# pic32.net
KiCad netlist of a schematic drawn in EAGLE
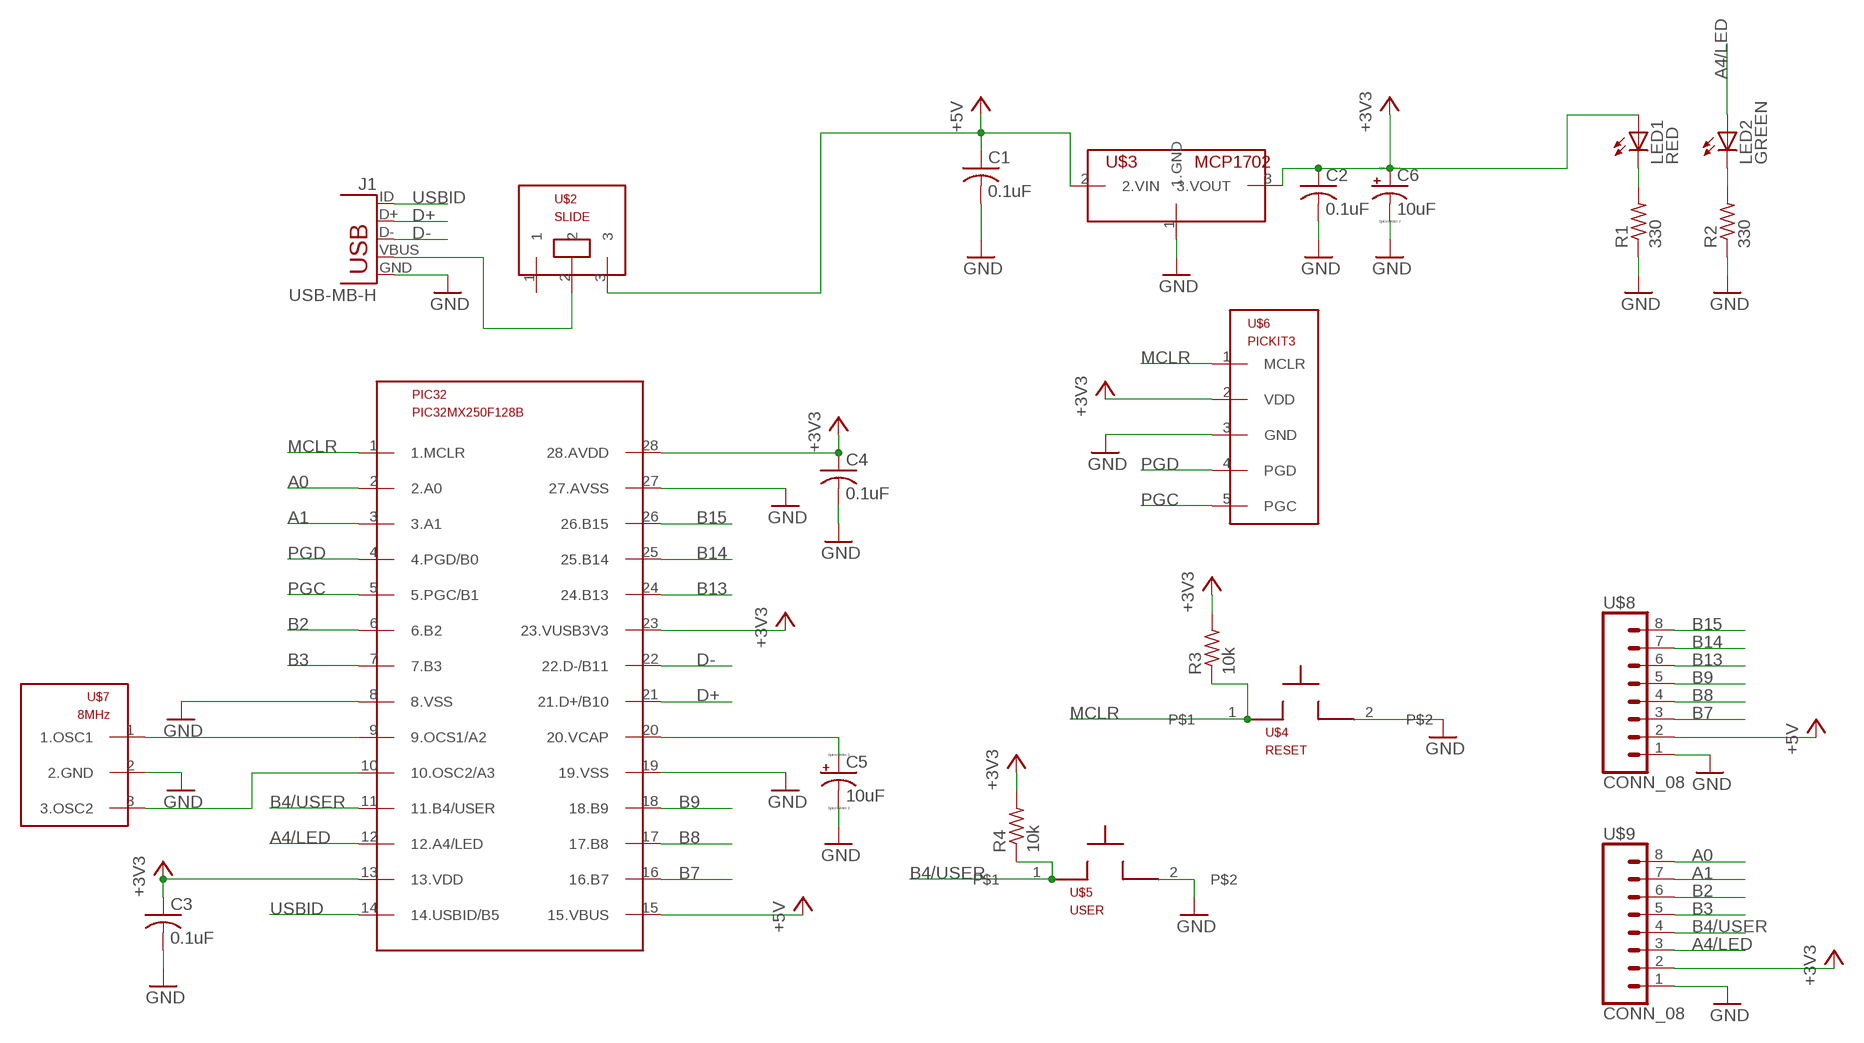
[diagram p0: schematic, sheet 1]

(export (version "E")
  (design (tool "Eeschema 10.0.6"))
  (components
    (comp (ref "C1")
      (value "0.1uF")
      (footprint "eagle-import:C025-025X050")
      (libsource (lib "eagle-import") (part "C-US025-025X050"))
    )
    (comp (ref "C2")
      (value "0.1uF")
      (footprint "eagle-import:C025-025X050")
      (libsource (lib "eagle-import") (part "C-US025-025X050"))
    )
    (comp (ref "C3")
      (value "0.1uF")
      (footprint "eagle-import:C025-025X050")
      (libsource (lib "eagle-import") (part "C-US025-025X050"))
    )
    (comp (ref "C4")
      (value "0.1uF")
      (footprint "eagle-import:C025-025X050")
      (libsource (lib "eagle-import") (part "C-US025-025X050"))
    )
    (comp (ref "C5")
      (value "10uF")
      (footprint "eagle-import:B45181B")
      (libsource (lib "eagle-import") (part "CPOL-USB45181B"))
    )
    (comp (ref "C6")
      (value "10uF")
      (footprint "eagle-import:B45181B")
      (libsource (lib "eagle-import") (part "CPOL-USB45181B"))
    )
    (comp (ref "J1")
      (value "USB-MB-H")
      (footprint "eagle-import:USB-MB-H")
      (libsource (lib "eagle-import") (part "USB-MB-H"))
    )
    (comp (ref "LED1")
      (value "RED")
      (footprint "eagle-import:LED3MM")
      (libsource (lib "eagle-import") (part "LED3MM"))
    )
    (comp (ref "LED2")
      (value "GREEN")
      (footprint "eagle-import:LED3MM")
      (libsource (lib "eagle-import") (part "LED3MM"))
    )
    (comp (ref "PIC32")
      (value "PIC32MX250F128B")
      (footprint "eagle-import:DIL28-3")
      (libsource (lib "eagle-import") (part "PIC32MX250F128B"))
    )
    (comp (ref "R1")
      (value "330")
      (footprint "eagle-import:0207_10")
      (libsource (lib "eagle-import") (part "R-US_0207/10"))
    )
    (comp (ref "R2")
      (value "330")
      (footprint "eagle-import:0207_10")
      (libsource (lib "eagle-import") (part "R-US_0207/10"))
    )
    (comp (ref "R3")
      (value "10k")
      (footprint "eagle-import:0207_10")
      (libsource (lib "eagle-import") (part "R-US_0207/10"))
    )
    (comp (ref "R4")
      (value "10k")
      (footprint "eagle-import:0207_10")
      (libsource (lib "eagle-import") (part "R-US_0207/10"))
    )
    (comp (ref "U$2")
      (value "SLIDE")
      (footprint "eagle-import:SLIDE")
      (libsource (lib "eagle-import") (part "SLIDE"))
    )
    (comp (ref "U$3")
      (value "MCP1702")
      (footprint "eagle-import:TO92")
      (libsource (lib "eagle-import") (part "MCP1702"))
    )
    (comp (ref "U$4")
      (value "RESET")
      (footprint "eagle-import:PB")
      (libsource (lib "eagle-import") (part "PB"))
    )
    (comp (ref "U$5")
      (value "USER")
      (footprint "eagle-import:PB")
      (libsource (lib "eagle-import") (part "PB"))
    )
    (comp (ref "U$6")
      (value "PICKIT3")
      (footprint "eagle-import:1X05")
      (libsource (lib "eagle-import") (part "PICKIT3"))
    )
    (comp (ref "U$7")
      (value "8MHz")
      (footprint "eagle-import:OSC")
      (libsource (lib "eagle-import") (part "OCS"))
    )
    (comp (ref "U$8")
      (value "CONN_08")
      (footprint "eagle-import:1X08")
      (libsource (lib "eagle-import") (part "CONN_08"))
    )
    (comp (ref "U$9")
      (value "CONN_08")
      (footprint "eagle-import:1X08")
      (libsource (lib "eagle-import") (part "CONN_08"))
    )
  )
  (nets
    (net (code "1") (name "+3V3") (class "Default")
      (node (ref "C2") (pin "1") (pinfunction "1_1") (pintype "passive"))
      (node (ref "C3") (pin "1") (pinfunction "1_1") (pintype "passive"))
      (node (ref "C4") (pin "1") (pinfunction "1_1") (pintype "passive"))
      (node (ref "C6") (pin "+") (pinfunction "+_+") (pintype "passive"))
      (node (ref "LED1") (pin "A") (pinfunction "A_A") (pintype "passive"))
      (node (ref "PIC32") (pin "13") (pinfunction "13.VDD_13") (pintype "bidirectional"))
      (node (ref "PIC32") (pin "23") (pinfunction "23.VUSB3V3_23") (pintype "bidirectional"))
      (node (ref "PIC32") (pin "28") (pinfunction "28.AVDD_28") (pintype "bidirectional"))
      (node (ref "R3") (pin "2") (pinfunction "2_2") (pintype "passive"))
      (node (ref "R4") (pin "2") (pinfunction "2_2") (pintype "passive"))
      (node (ref "U$3") (pin "3") (pinfunction "3.VOUT_3") (pintype "bidirectional"))
      (node (ref "U$6") (pin "2") (pinfunction "VDD_2") (pintype "bidirectional"))
      (node (ref "U$9") (pin "2") (pinfunction "2_2") (pintype "passive"))
    )
    (net (code "2") (name "+5V") (class "Default")
      (node (ref "C1") (pin "1") (pinfunction "1_1") (pintype "passive"))
      (node (ref "PIC32") (pin "15") (pinfunction "15.VBUS_15") (pintype "bidirectional"))
      (node (ref "U$2") (pin "3") (pinfunction "3_3") (pintype "bidirectional"))
      (node (ref "U$3") (pin "2") (pinfunction "2.VIN_2") (pintype "bidirectional"))
      (node (ref "U$8") (pin "2") (pinfunction "2_2") (pintype "passive"))
    )
    (net (code "3") (name "/A0") (class "Default")
      (node (ref "PIC32") (pin "2") (pinfunction "2.A0_2") (pintype "bidirectional"))
      (node (ref "U$9") (pin "8") (pinfunction "8_8") (pintype "passive"))
    )
    (net (code "4") (name "/A1") (class "Default")
      (node (ref "PIC32") (pin "3") (pinfunction "3.A1_3") (pintype "bidirectional"))
      (node (ref "U$9") (pin "7") (pinfunction "7_7") (pintype "passive"))
    )
    (net (code "5") (name "/A4{slash}LED") (class "Default")
      (node (ref "LED2") (pin "A") (pinfunction "A_A") (pintype "passive"))
      (node (ref "PIC32") (pin "12") (pinfunction "12.A4/LED_12") (pintype "bidirectional"))
      (node (ref "U$9") (pin "3") (pinfunction "3_3") (pintype "passive"))
    )
    (net (code "6") (name "/B2") (class "Default")
      (node (ref "PIC32") (pin "6") (pinfunction "6.B2_6") (pintype "bidirectional"))
      (node (ref "U$9") (pin "6") (pinfunction "6_6") (pintype "passive"))
    )
    (net (code "7") (name "/B3") (class "Default")
      (node (ref "PIC32") (pin "7") (pinfunction "7.B3_7") (pintype "bidirectional"))
      (node (ref "U$9") (pin "5") (pinfunction "5_5") (pintype "passive"))
    )
    (net (code "8") (name "/B4{slash}USER") (class "Default")
      (node (ref "PIC32") (pin "11") (pinfunction "11.B4/USER_11") (pintype "bidirectional"))
      (node (ref "R4") (pin "1") (pinfunction "1_1") (pintype "passive"))
      (node (ref "U$5") (pin "1") (pinfunction "P$1_1") (pintype "bidirectional"))
      (node (ref "U$9") (pin "4") (pinfunction "4_4") (pintype "passive"))
    )
    (net (code "9") (name "/B7") (class "Default")
      (node (ref "PIC32") (pin "16") (pinfunction "16.B7_16") (pintype "bidirectional"))
      (node (ref "U$8") (pin "3") (pinfunction "3_3") (pintype "passive"))
    )
    (net (code "10") (name "/B8") (class "Default")
      (node (ref "PIC32") (pin "17") (pinfunction "17.B8_17") (pintype "bidirectional"))
      (node (ref "U$8") (pin "4") (pinfunction "4_4") (pintype "passive"))
    )
    (net (code "11") (name "/B9") (class "Default")
      (node (ref "PIC32") (pin "18") (pinfunction "18.B9_18") (pintype "bidirectional"))
      (node (ref "U$8") (pin "5") (pinfunction "5_5") (pintype "passive"))
    )
    (net (code "12") (name "/B13") (class "Default")
      (node (ref "PIC32") (pin "24") (pinfunction "24.B13_24") (pintype "bidirectional"))
      (node (ref "U$8") (pin "6") (pinfunction "6_6") (pintype "passive"))
    )
    (net (code "13") (name "/B14") (class "Default")
      (node (ref "PIC32") (pin "25") (pinfunction "25.B14_25") (pintype "bidirectional"))
      (node (ref "U$8") (pin "7") (pinfunction "7_7") (pintype "passive"))
    )
    (net (code "14") (name "/B15") (class "Default")
      (node (ref "PIC32") (pin "26") (pinfunction "26.B15_26") (pintype "bidirectional"))
      (node (ref "U$8") (pin "8") (pinfunction "8_8") (pintype "passive"))
    )
    (net (code "15") (name "/D+") (class "Default")
      (node (ref "J1") (pin "D+") (pinfunction "D+_D+") (pintype "bidirectional"))
      (node (ref "PIC32") (pin "21") (pinfunction "21.D+/B10_21") (pintype "bidirectional"))
    )
    (net (code "16") (name "/D-") (class "Default")
      (node (ref "J1") (pin "D-") (pinfunction "D-_D-") (pintype "bidirectional"))
      (node (ref "PIC32") (pin "22") (pinfunction "22.D-/B11_22") (pintype "bidirectional"))
    )
    (net (code "17") (name "/MCLR") (class "Default")
      (node (ref "PIC32") (pin "1") (pinfunction "1.MCLR_1") (pintype "bidirectional"))
      (node (ref "R3") (pin "1") (pinfunction "1_1") (pintype "passive"))
      (node (ref "U$4") (pin "1") (pinfunction "P$1_1") (pintype "bidirectional"))
      (node (ref "U$6") (pin "1") (pinfunction "MCLR_1") (pintype "bidirectional"))
    )
    (net (code "18") (name "/PGC") (class "Default")
      (node (ref "PIC32") (pin "5") (pinfunction "5.PGC/B1_5") (pintype "bidirectional"))
      (node (ref "U$6") (pin "5") (pinfunction "PGC_5") (pintype "bidirectional"))
    )
    (net (code "19") (name "/PGD") (class "Default")
      (node (ref "PIC32") (pin "4") (pinfunction "4.PGD/B0_4") (pintype "bidirectional"))
      (node (ref "U$6") (pin "4") (pinfunction "PGD_4") (pintype "bidirectional"))
    )
    (net (code "20") (name "/USBID") (class "Default")
      (node (ref "J1") (pin "ID") (pinfunction "ID_ID") (pintype "bidirectional"))
      (node (ref "PIC32") (pin "14") (pinfunction "14.USBID/B5_14") (pintype "bidirectional"))
    )
    (net (code "21") (name "GND") (class "Default")
      (node (ref "C1") (pin "2") (pinfunction "2_2") (pintype "passive"))
      (node (ref "C2") (pin "2") (pinfunction "2_2") (pintype "passive"))
      (node (ref "C3") (pin "2") (pinfunction "2_2") (pintype "passive"))
      (node (ref "C4") (pin "2") (pinfunction "2_2") (pintype "passive"))
      (node (ref "C5") (pin "-") (pinfunction "-_-") (pintype "passive"))
      (node (ref "C6") (pin "-") (pinfunction "-_-") (pintype "passive"))
      (node (ref "J1") (pin "GND") (pinfunction "GND_GND") (pintype "bidirectional"))
      (node (ref "PIC32") (pin "19") (pinfunction "19.VSS_19") (pintype "bidirectional"))
      (node (ref "PIC32") (pin "27") (pinfunction "27.AVSS_27") (pintype "bidirectional"))
      (node (ref "PIC32") (pin "8") (pinfunction "8.VSS_8") (pintype "bidirectional"))
      (node (ref "R1") (pin "1") (pinfunction "1_1") (pintype "passive"))
      (node (ref "R2") (pin "1") (pinfunction "1_1") (pintype "passive"))
      (node (ref "U$3") (pin "1") (pinfunction "1.GND_1") (pintype "bidirectional"))
      (node (ref "U$4") (pin "2") (pinfunction "P$2_2") (pintype "bidirectional"))
      (node (ref "U$5") (pin "2") (pinfunction "P$2_2") (pintype "bidirectional"))
      (node (ref "U$6") (pin "3") (pinfunction "GND_3") (pintype "bidirectional"))
      (node (ref "U$7") (pin "2") (pinfunction "2.GND_2") (pintype "bidirectional"))
      (node (ref "U$8") (pin "1") (pinfunction "1_1") (pintype "passive"))
      (node (ref "U$9") (pin "1") (pinfunction "1_1") (pintype "passive"))
    )
    (net (code "22") (name "Net-(J1-PadVBUS)") (class "Default")
      (node (ref "J1") (pin "VBUS") (pinfunction "VBUS_VBUS") (pintype "bidirectional"))
      (node (ref "U$2") (pin "2") (pinfunction "2_2") (pintype "bidirectional"))
    )
    (net (code "23") (name "Net-(LED1-C)") (class "Default")
      (node (ref "LED1") (pin "K") (pinfunction "C_K") (pintype "passive"))
      (node (ref "R1") (pin "2") (pinfunction "2_2") (pintype "passive"))
    )
    (net (code "24") (name "Net-(LED2-C)") (class "Default")
      (node (ref "LED2") (pin "K") (pinfunction "C_K") (pintype "passive"))
      (node (ref "R2") (pin "2") (pinfunction "2_2") (pintype "passive"))
    )
    (net (code "25") (name "Net-(PIC32-9.OCS1{slash}A2)") (class "Default")
      (node (ref "PIC32") (pin "9") (pinfunction "9.OCS1/A2_9") (pintype "bidirectional"))
      (node (ref "U$7") (pin "1") (pinfunction "1.OSC1_1") (pintype "bidirectional"))
    )
    (net (code "26") (name "Net-(PIC32-10.OSC2{slash}A3)") (class "Default")
      (node (ref "PIC32") (pin "10") (pinfunction "10.OSC2/A3_10") (pintype "bidirectional"))
      (node (ref "U$7") (pin "3") (pinfunction "3.OSC2_3") (pintype "bidirectional"))
    )
    (net (code "27") (name "Net-(PIC32-20.VCAP)") (class "Default")
      (node (ref "C5") (pin "+") (pinfunction "+_+") (pintype "passive"))
      (node (ref "PIC32") (pin "20") (pinfunction "20.VCAP_20") (pintype "bidirectional"))
    )
    (net (code "28") (name "unconnected-(U$2-Pad1)") (class "Default")
      (node (ref "U$2") (pin "1") (pinfunction "1_1") (pintype "bidirectional"))
    )
  )
)
